# matrix-cell.net
KiCad netlist of a schematic drawn in EAGLE
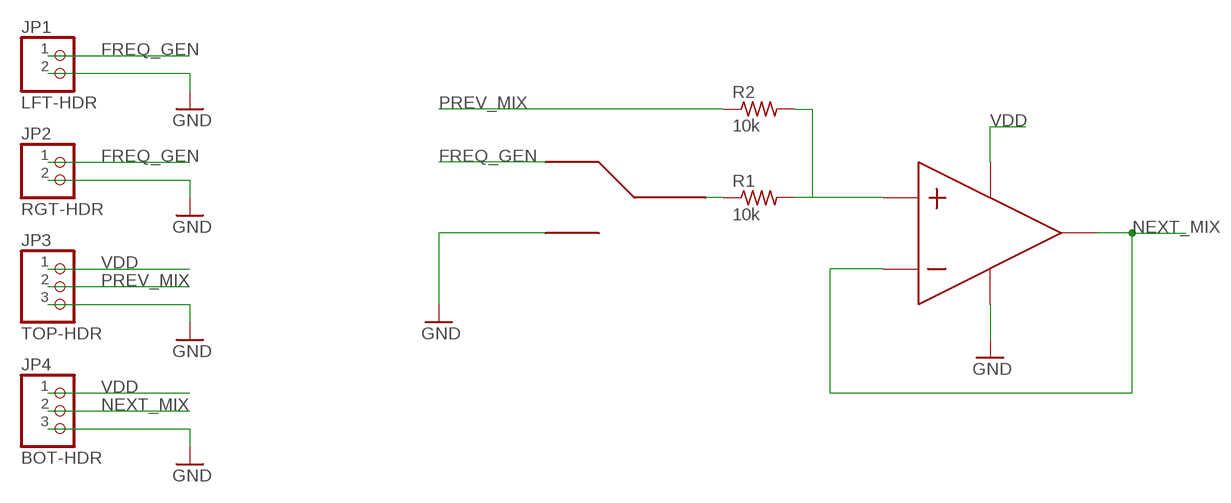
[diagram p0: schematic, sheet 1]

(export (version "E")
  (design (tool "Eeschema 10.0.6"))
  (components
    (comp (ref "JP1")
      (value "LFT-HDR")
      (footprint "eagle-import:1X02_90")
      (libsource (lib "eagle-import") (part "PINHD-1X2/90"))
    )
    (comp (ref "JP2")
      (value "RGT-HDR")
      (footprint "eagle-import:1X02_90")
      (libsource (lib "eagle-import") (part "PINHD-1X2/90"))
    )
    (comp (ref "JP3")
      (value "TOP-HDR")
      (footprint "eagle-import:1X03_90")
      (libsource (lib "eagle-import") (part "PINHD-1X3/90"))
    )
    (comp (ref "JP4")
      (value "BOT-HDR")
      (footprint "eagle-import:1X03_90")
      (libsource (lib "eagle-import") (part "PINHD-1X3/90"))
    )
    (comp (ref "R1")
      (value "10k")
      (footprint "eagle-import:R1206")
      (libsource (lib "eagle-import") (part "R-US_R1206"))
    )
    (comp (ref "R2")
      (value "10k")
      (footprint "eagle-import:R1206")
      (libsource (lib "eagle-import") (part "R-US_R1206"))
    )
    (comp (ref "U$1")
      (value "RA1-SWITCH")
      (footprint "eagle-import:RA11131100-SWITCH")
      (libsource (lib "eagle-import") (part "RA1-SWITCH"))
    )
    (comp (ref "U$2")
      (value "MCP4162-OPAMP")
      (footprint "eagle-import:SO08")
      (libsource (lib "eagle-import") (part "MCP4162-OPAMP"))
    )
  )
  (nets
    (net (code "1") (name "/FREQ_GEN") (class "Default")
      (node (ref "JP1") (pin "1") (pinfunction "1_1") (pintype "passive"))
      (node (ref "JP2") (pin "1") (pinfunction "1_1") (pintype "passive"))
      (node (ref "U$1") (pin "R") (pinfunction "NO_R") (pintype "bidirectional"))
    )
    (net (code "2") (name "/NEXT_MIX") (class "Default")
      (node (ref "JP4") (pin "2") (pinfunction "2_2") (pintype "passive"))
      (node (ref "U$2") (pin "2") (pinfunction "INV_2") (pintype "bidirectional"))
      (node (ref "U$2") (pin "6") (pinfunction "OUT_6") (pintype "bidirectional"))
    )
    (net (code "3") (name "/PREV_MIX") (class "Default")
      (node (ref "JP3") (pin "2") (pinfunction "2_2") (pintype "passive"))
      (node (ref "R2") (pin "1") (pinfunction "1_1") (pintype "passive"))
    )
    (net (code "4") (name "/VDD") (class "Default")
      (node (ref "JP3") (pin "1") (pinfunction "1_1") (pintype "passive"))
      (node (ref "JP4") (pin "1") (pinfunction "1_1") (pintype "passive"))
      (node (ref "U$2") (pin "7") (pinfunction "VDD_7") (pintype "bidirectional"))
    )
    (net (code "5") (name "GND") (class "Default")
      (node (ref "JP1") (pin "2") (pinfunction "2_2") (pintype "passive"))
      (node (ref "JP2") (pin "2") (pinfunction "2_2") (pintype "passive"))
      (node (ref "JP3") (pin "3") (pinfunction "3_3") (pintype "passive"))
      (node (ref "JP4") (pin "3") (pinfunction "3_3") (pintype "passive"))
      (node (ref "U$1") (pin "L") (pinfunction "NC_L") (pintype "bidirectional"))
      (node (ref "U$2") (pin "4") (pinfunction "VSS_4") (pintype "bidirectional"))
    )
    (net (code "6") (name "Net-(U$1-COMM)") (class "Default")
      (node (ref "R1") (pin "1") (pinfunction "1_1") (pintype "passive"))
      (node (ref "U$1") (pin "C") (pinfunction "COMM_C") (pintype "bidirectional"))
    )
    (net (code "7") (name "Net-(U$2-NON-INV)") (class "Default")
      (node (ref "R1") (pin "2") (pinfunction "2_2") (pintype "passive"))
      (node (ref "R2") (pin "2") (pinfunction "2_2") (pintype "passive"))
      (node (ref "U$2") (pin "3") (pinfunction "NON-INV_3") (pintype "bidirectional"))
    )
  )
)
